# numpad.net
KiCad netlist of a schematic drawn in EAGLE
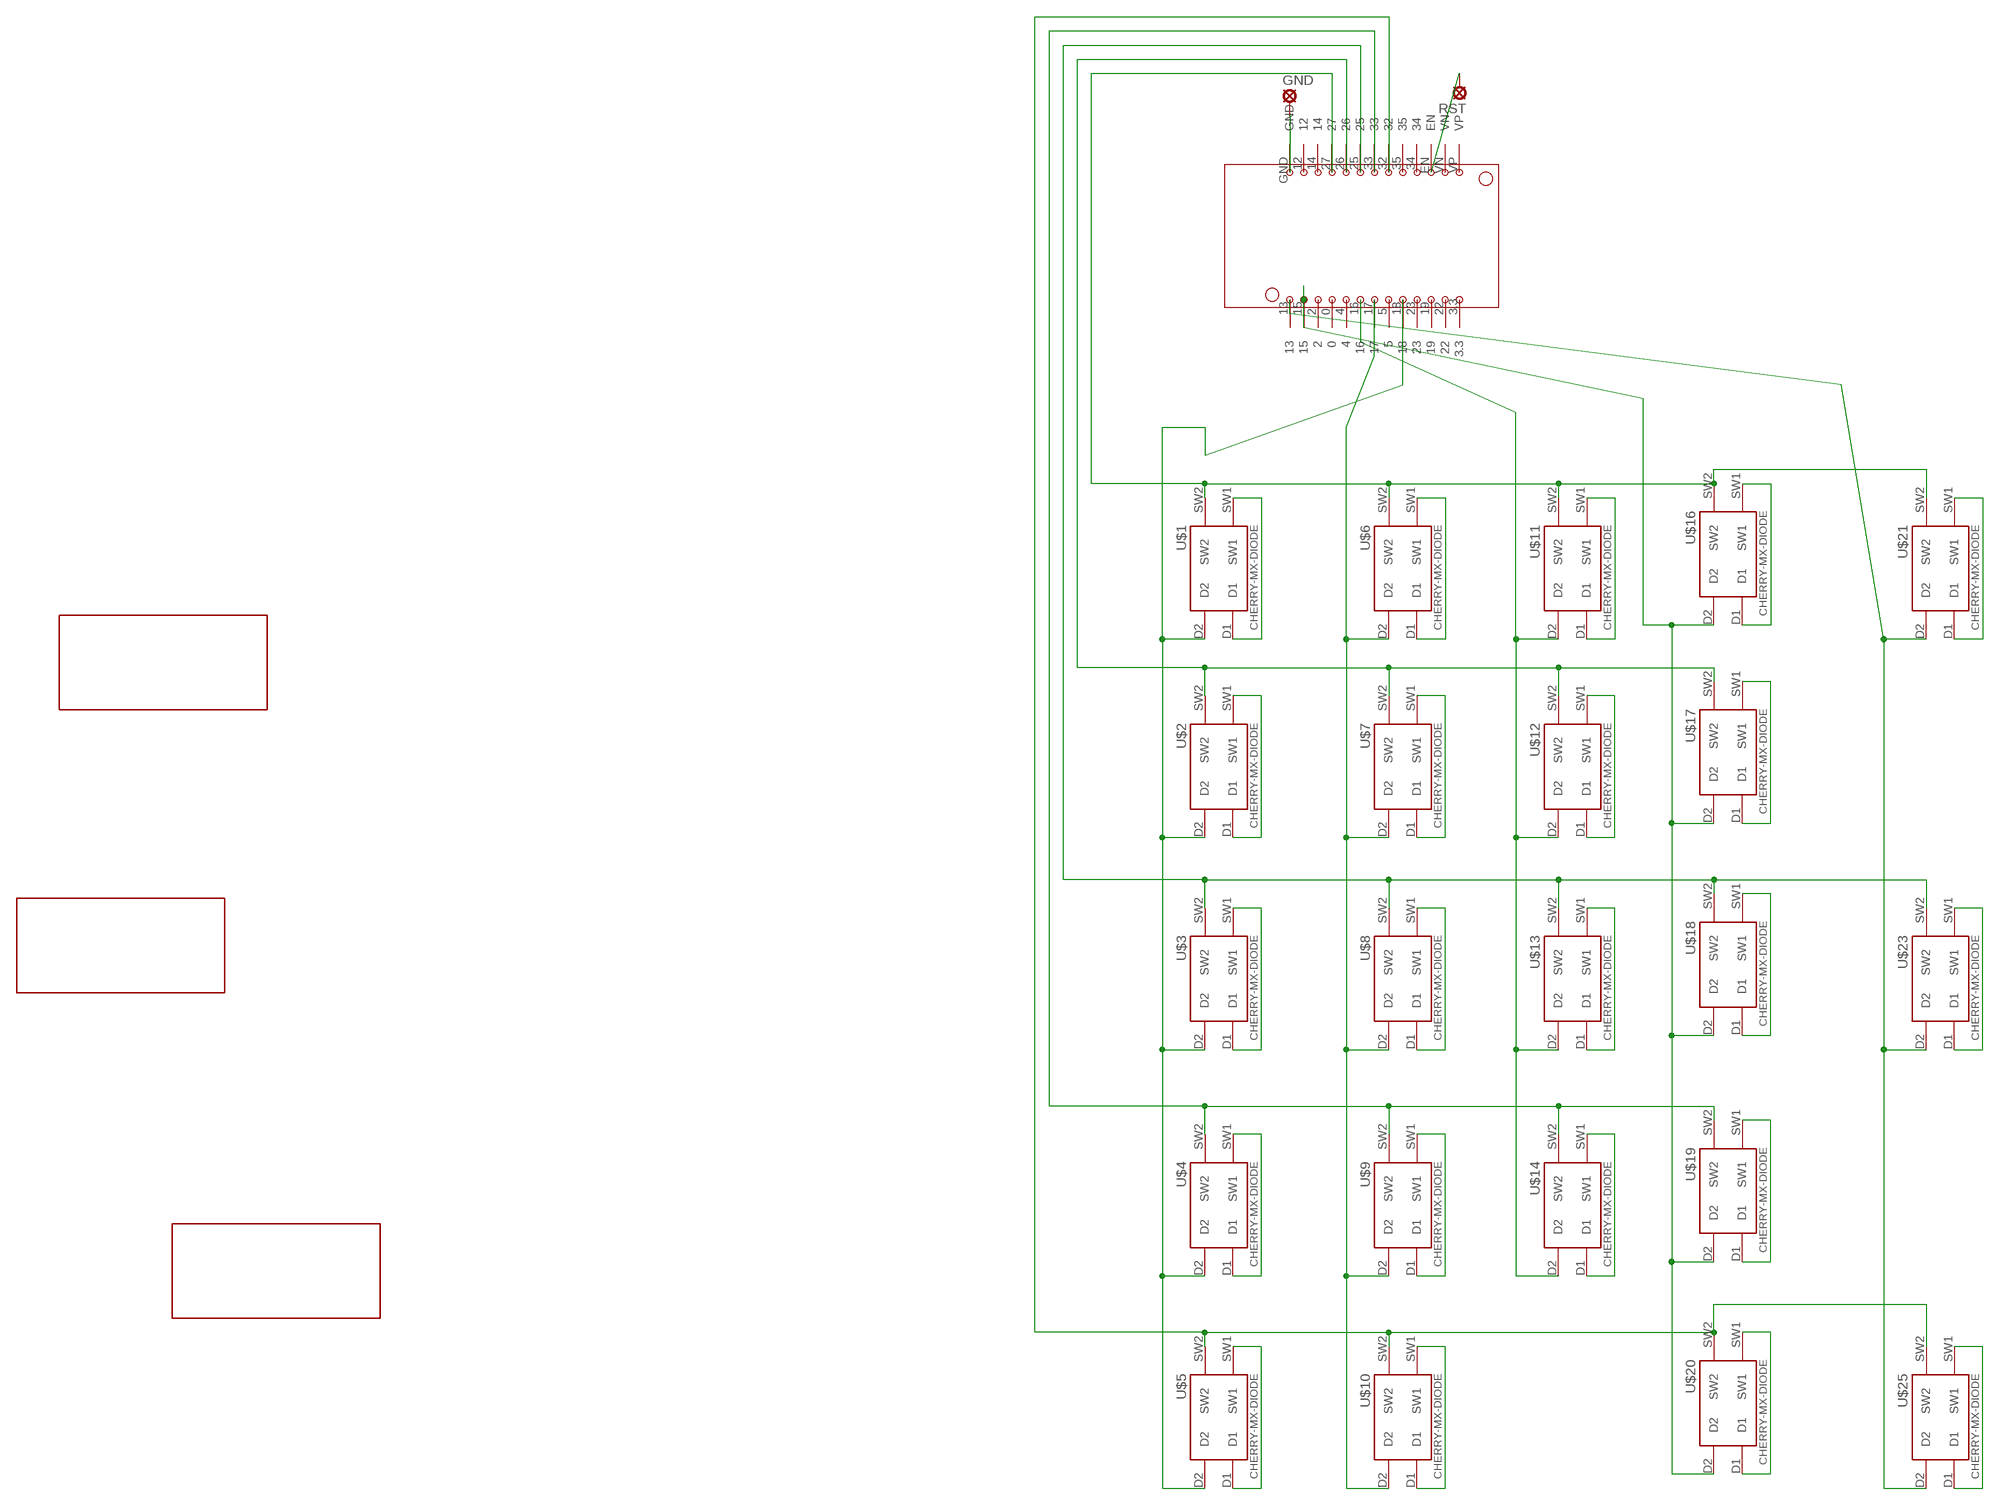
[diagram p0: schematic, sheet 1]

(export (version "E")
  (design (tool "Eeschema 10.0.6"))
  (components
    (comp (ref "GND")
      (value "LSP10")
      (footprint "eagle-import:LSP10")
      (libsource (lib "eagle-import") (part "LSP10"))
    )
    (comp (ref "RST")
      (value "LSP10")
      (footprint "eagle-import:LSP10")
      (libsource (lib "eagle-import") (part "LSP10"))
    )
    (comp (ref "U$1")
      (value "CHERRY-MX-DIODE")
      (footprint "eagle-import:CHERRY-MX-DIODE")
      (libsource (lib "eagle-import") (part "CHERRY-MX-DIODE"))
    )
    (comp (ref "U$2")
      (value "CHERRY-MX-DIODE")
      (footprint "eagle-import:CHERRY-MX-DIODE")
      (libsource (lib "eagle-import") (part "CHERRY-MX-DIODE"))
    )
    (comp (ref "U$3")
      (value "CHERRY-MX-DIODE")
      (footprint "eagle-import:CHERRY-MX-DIODE")
      (libsource (lib "eagle-import") (part "CHERRY-MX-DIODE"))
    )
    (comp (ref "U$4")
      (value "CHERRY-MX-DIODE")
      (footprint "eagle-import:CHERRY-MX-DIODE")
      (libsource (lib "eagle-import") (part "CHERRY-MX-DIODE"))
    )
    (comp (ref "U$5")
      (value "CHERRY-MX-DIODE")
      (footprint "eagle-import:CHERRY-MX-DIODE")
      (libsource (lib "eagle-import") (part "CHERRY-MX-DIODE"))
    )
    (comp (ref "U$6")
      (value "CHERRY-MX-DIODE")
      (footprint "eagle-import:CHERRY-MX-DIODE")
      (libsource (lib "eagle-import") (part "CHERRY-MX-DIODE"))
    )
    (comp (ref "U$7")
      (value "CHERRY-MX-DIODE")
      (footprint "eagle-import:CHERRY-MX-DIODE")
      (libsource (lib "eagle-import") (part "CHERRY-MX-DIODE"))
    )
    (comp (ref "U$8")
      (value "CHERRY-MX-DIODE")
      (footprint "eagle-import:CHERRY-MX-DIODE")
      (libsource (lib "eagle-import") (part "CHERRY-MX-DIODE"))
    )
    (comp (ref "U$9")
      (value "CHERRY-MX-DIODE")
      (footprint "eagle-import:CHERRY-MX-DIODE")
      (libsource (lib "eagle-import") (part "CHERRY-MX-DIODE"))
    )
    (comp (ref "U$10")
      (value "CHERRY-MX-DIODE")
      (footprint "eagle-import:CHERRY-MX-DIODE")
      (libsource (lib "eagle-import") (part "CHERRY-MX-DIODE"))
    )
    (comp (ref "U$11")
      (value "CHERRY-MX-DIODE")
      (footprint "eagle-import:CHERRY-MX-DIODE")
      (libsource (lib "eagle-import") (part "CHERRY-MX-DIODE"))
    )
    (comp (ref "U$12")
      (value "CHERRY-MX-DIODE")
      (footprint "eagle-import:CHERRY-MX-DIODE")
      (libsource (lib "eagle-import") (part "CHERRY-MX-DIODE"))
    )
    (comp (ref "U$13")
      (value "CHERRY-MX-DIODE")
      (footprint "eagle-import:CHERRY-MX-DIODE")
      (libsource (lib "eagle-import") (part "CHERRY-MX-DIODE"))
    )
    (comp (ref "U$14")
      (value "CHERRY-MX-DIODE")
      (footprint "eagle-import:CHERRY-MX-DIODE")
      (libsource (lib "eagle-import") (part "CHERRY-MX-DIODE"))
    )
    (comp (ref "U$15")
      (value "2U")
      (footprint "eagle-import:2U")
      (libsource (lib "eagle-import") (part "2U"))
    )
    (comp (ref "U$16")
      (value "CHERRY-MX-DIODE")
      (footprint "eagle-import:CHERRY-MX-DIODE")
      (libsource (lib "eagle-import") (part "CHERRY-MX-DIODE"))
    )
    (comp (ref "U$17")
      (value "CHERRY-MX-DIODE")
      (footprint "eagle-import:CHERRY-MX-DIODE")
      (libsource (lib "eagle-import") (part "CHERRY-MX-DIODE"))
    )
    (comp (ref "U$18")
      (value "CHERRY-MX-DIODE")
      (footprint "eagle-import:CHERRY-MX-DIODE")
      (libsource (lib "eagle-import") (part "CHERRY-MX-DIODE"))
    )
    (comp (ref "U$19")
      (value "CHERRY-MX-DIODE")
      (footprint "eagle-import:CHERRY-MX-DIODE")
      (libsource (lib "eagle-import") (part "CHERRY-MX-DIODE"))
    )
    (comp (ref "U$20")
      (value "CHERRY-MX-DIODE")
      (footprint "eagle-import:CHERRY-MX-DIODE")
      (libsource (lib "eagle-import") (part "CHERRY-MX-DIODE"))
    )
    (comp (ref "U$21")
      (value "CHERRY-MX-DIODE")
      (footprint "eagle-import:CHERRY-MX-DIODE")
      (libsource (lib "eagle-import") (part "CHERRY-MX-DIODE"))
    )
    (comp (ref "U$22")
      (value "2U")
      (footprint "eagle-import:2U")
      (libsource (lib "eagle-import") (part "2U"))
    )
    (comp (ref "U$23")
      (value "CHERRY-MX-DIODE")
      (footprint "eagle-import:CHERRY-MX-DIODE")
      (libsource (lib "eagle-import") (part "CHERRY-MX-DIODE"))
    )
    (comp (ref "U$24")
      (value "2U")
      (footprint "eagle-import:2U")
      (libsource (lib "eagle-import") (part "2U"))
    )
    (comp (ref "U$25")
      (value "CHERRY-MX-DIODE")
      (footprint "eagle-import:CHERRY-MX-DIODE")
      (libsource (lib "eagle-import") (part "CHERRY-MX-DIODE"))
    )
    (comp (ref "U$27")
      (value "ESP32OFFBRAND")
      (footprint "eagle-import:ESP32OFFBRAND")
      (libsource (lib "eagle-import") (part "ESP32OFFBRAND"))
    )
  )
  (nets
    (net (code "1") (name "Net-(GND-PadMP)") (class "Default")
      (node (ref "GND") (pin "MP") (pinfunction "MP_MP") (pintype "passive"))
      (node (ref "U$27") (pin "GND") (pinfunction "GND_GND") (pintype "bidirectional"))
    )
    (net (code "2") (name "Net-(RST-PadMP)") (class "Default")
      (node (ref "RST") (pin "MP") (pinfunction "MP_MP") (pintype "passive"))
      (node (ref "U$27") (pin "EN") (pinfunction "EN_EN") (pintype "bidirectional"))
    )
    (net (code "3") (name "Net-(U$1-PadD1)") (class "Default")
      (node (ref "U$1") (pin "D1") (pinfunction "D1_D1") (pintype "bidirectional"))
      (node (ref "U$1") (pin "SW1") (pinfunction "SW1_SW1") (pintype "bidirectional"))
    )
    (net (code "4") (name "Net-(U$1-PadD2)") (class "Default")
      (node (ref "U$1") (pin "D2") (pinfunction "D2_D2") (pintype "bidirectional"))
      (node (ref "U$2") (pin "D2") (pinfunction "D2_D2") (pintype "bidirectional"))
      (node (ref "U$27") (pin "18") (pinfunction "18_18") (pintype "bidirectional"))
      (node (ref "U$3") (pin "D2") (pinfunction "D2_D2") (pintype "bidirectional"))
      (node (ref "U$4") (pin "D2") (pinfunction "D2_D2") (pintype "bidirectional"))
      (node (ref "U$5") (pin "D2") (pinfunction "D2_D2") (pintype "bidirectional"))
    )
    (net (code "5") (name "Net-(U$1-PadSW2)") (class "Default")
      (node (ref "U$1") (pin "SW2") (pinfunction "SW2_SW2") (pintype "bidirectional"))
      (node (ref "U$11") (pin "SW2") (pinfunction "SW2_SW2") (pintype "bidirectional"))
      (node (ref "U$16") (pin "SW2") (pinfunction "SW2_SW2") (pintype "bidirectional"))
      (node (ref "U$21") (pin "SW2") (pinfunction "SW2_SW2") (pintype "bidirectional"))
      (node (ref "U$27") (pin "27") (pinfunction "27_27") (pintype "bidirectional"))
      (node (ref "U$6") (pin "SW2") (pinfunction "SW2_SW2") (pintype "bidirectional"))
    )
    (net (code "6") (name "Net-(U$2-PadD1)") (class "Default")
      (node (ref "U$2") (pin "D1") (pinfunction "D1_D1") (pintype "bidirectional"))
      (node (ref "U$2") (pin "SW1") (pinfunction "SW1_SW1") (pintype "bidirectional"))
    )
    (net (code "7") (name "Net-(U$3-PadD1)") (class "Default")
      (node (ref "U$3") (pin "D1") (pinfunction "D1_D1") (pintype "bidirectional"))
      (node (ref "U$3") (pin "SW1") (pinfunction "SW1_SW1") (pintype "bidirectional"))
    )
    (net (code "8") (name "Net-(U$4-PadD1)") (class "Default")
      (node (ref "U$4") (pin "D1") (pinfunction "D1_D1") (pintype "bidirectional"))
      (node (ref "U$4") (pin "SW1") (pinfunction "SW1_SW1") (pintype "bidirectional"))
    )
    (net (code "9") (name "Net-(U$5-PadD1)") (class "Default")
      (node (ref "U$5") (pin "D1") (pinfunction "D1_D1") (pintype "bidirectional"))
      (node (ref "U$5") (pin "SW1") (pinfunction "SW1_SW1") (pintype "bidirectional"))
    )
    (net (code "10") (name "Net-(U$6-PadD1)") (class "Default")
      (node (ref "U$6") (pin "D1") (pinfunction "D1_D1") (pintype "bidirectional"))
      (node (ref "U$6") (pin "SW1") (pinfunction "SW1_SW1") (pintype "bidirectional"))
    )
    (net (code "11") (name "Net-(U$7-PadD1)") (class "Default")
      (node (ref "U$7") (pin "D1") (pinfunction "D1_D1") (pintype "bidirectional"))
      (node (ref "U$7") (pin "SW1") (pinfunction "SW1_SW1") (pintype "bidirectional"))
    )
    (net (code "12") (name "Net-(U$8-PadD1)") (class "Default")
      (node (ref "U$8") (pin "D1") (pinfunction "D1_D1") (pintype "bidirectional"))
      (node (ref "U$8") (pin "SW1") (pinfunction "SW1_SW1") (pintype "bidirectional"))
    )
    (net (code "13") (name "Net-(U$9-PadD1)") (class "Default")
      (node (ref "U$9") (pin "D1") (pinfunction "D1_D1") (pintype "bidirectional"))
      (node (ref "U$9") (pin "SW1") (pinfunction "SW1_SW1") (pintype "bidirectional"))
    )
    (net (code "14") (name "Net-(U$10-PadD1)") (class "Default")
      (node (ref "U$10") (pin "D1") (pinfunction "D1_D1") (pintype "bidirectional"))
      (node (ref "U$10") (pin "SW1") (pinfunction "SW1_SW1") (pintype "bidirectional"))
    )
    (net (code "15") (name "Net-(U$10-PadD2)") (class "Default")
      (node (ref "U$10") (pin "D2") (pinfunction "D2_D2") (pintype "bidirectional"))
      (node (ref "U$27") (pin "17") (pinfunction "17_17") (pintype "bidirectional"))
      (node (ref "U$6") (pin "D2") (pinfunction "D2_D2") (pintype "bidirectional"))
      (node (ref "U$7") (pin "D2") (pinfunction "D2_D2") (pintype "bidirectional"))
      (node (ref "U$8") (pin "D2") (pinfunction "D2_D2") (pintype "bidirectional"))
      (node (ref "U$9") (pin "D2") (pinfunction "D2_D2") (pintype "bidirectional"))
    )
    (net (code "16") (name "Net-(U$10-PadSW2)") (class "Default")
      (node (ref "U$10") (pin "SW2") (pinfunction "SW2_SW2") (pintype "bidirectional"))
      (node (ref "U$20") (pin "SW2") (pinfunction "SW2_SW2") (pintype "bidirectional"))
      (node (ref "U$25") (pin "SW2") (pinfunction "SW2_SW2") (pintype "bidirectional"))
      (node (ref "U$27") (pin "32") (pinfunction "32_32") (pintype "bidirectional"))
      (node (ref "U$5") (pin "SW2") (pinfunction "SW2_SW2") (pintype "bidirectional"))
    )
    (net (code "17") (name "Net-(U$11-PadD1)") (class "Default")
      (node (ref "U$11") (pin "D1") (pinfunction "D1_D1") (pintype "bidirectional"))
      (node (ref "U$11") (pin "SW1") (pinfunction "SW1_SW1") (pintype "bidirectional"))
    )
    (net (code "18") (name "Net-(U$11-PadD2)") (class "Default")
      (node (ref "U$11") (pin "D2") (pinfunction "D2_D2") (pintype "bidirectional"))
      (node (ref "U$12") (pin "D2") (pinfunction "D2_D2") (pintype "bidirectional"))
      (node (ref "U$13") (pin "D2") (pinfunction "D2_D2") (pintype "bidirectional"))
      (node (ref "U$14") (pin "D2") (pinfunction "D2_D2") (pintype "bidirectional"))
      (node (ref "U$27") (pin "16") (pinfunction "16_16") (pintype "bidirectional"))
    )
    (net (code "19") (name "Net-(U$12-PadD1)") (class "Default")
      (node (ref "U$12") (pin "D1") (pinfunction "D1_D1") (pintype "bidirectional"))
      (node (ref "U$12") (pin "SW1") (pinfunction "SW1_SW1") (pintype "bidirectional"))
    )
    (net (code "20") (name "Net-(U$12-PadSW2)") (class "Default")
      (node (ref "U$12") (pin "SW2") (pinfunction "SW2_SW2") (pintype "bidirectional"))
      (node (ref "U$17") (pin "SW2") (pinfunction "SW2_SW2") (pintype "bidirectional"))
      (node (ref "U$2") (pin "SW2") (pinfunction "SW2_SW2") (pintype "bidirectional"))
      (node (ref "U$27") (pin "26") (pinfunction "26_26") (pintype "bidirectional"))
      (node (ref "U$7") (pin "SW2") (pinfunction "SW2_SW2") (pintype "bidirectional"))
    )
    (net (code "21") (name "Net-(U$13-PadD1)") (class "Default")
      (node (ref "U$13") (pin "D1") (pinfunction "D1_D1") (pintype "bidirectional"))
      (node (ref "U$13") (pin "SW1") (pinfunction "SW1_SW1") (pintype "bidirectional"))
    )
    (net (code "22") (name "Net-(U$13-PadSW2)") (class "Default")
      (node (ref "U$13") (pin "SW2") (pinfunction "SW2_SW2") (pintype "bidirectional"))
      (node (ref "U$18") (pin "SW2") (pinfunction "SW2_SW2") (pintype "bidirectional"))
      (node (ref "U$23") (pin "SW2") (pinfunction "SW2_SW2") (pintype "bidirectional"))
      (node (ref "U$27") (pin "25") (pinfunction "25_25") (pintype "bidirectional"))
      (node (ref "U$3") (pin "SW2") (pinfunction "SW2_SW2") (pintype "bidirectional"))
      (node (ref "U$8") (pin "SW2") (pinfunction "SW2_SW2") (pintype "bidirectional"))
    )
    (net (code "23") (name "Net-(U$14-PadD1)") (class "Default")
      (node (ref "U$14") (pin "D1") (pinfunction "D1_D1") (pintype "bidirectional"))
      (node (ref "U$14") (pin "SW1") (pinfunction "SW1_SW1") (pintype "bidirectional"))
    )
    (net (code "24") (name "Net-(U$14-PadSW2)") (class "Default")
      (node (ref "U$14") (pin "SW2") (pinfunction "SW2_SW2") (pintype "bidirectional"))
      (node (ref "U$19") (pin "SW2") (pinfunction "SW2_SW2") (pintype "bidirectional"))
      (node (ref "U$27") (pin "33") (pinfunction "33_33") (pintype "bidirectional"))
      (node (ref "U$4") (pin "SW2") (pinfunction "SW2_SW2") (pintype "bidirectional"))
      (node (ref "U$9") (pin "SW2") (pinfunction "SW2_SW2") (pintype "bidirectional"))
    )
    (net (code "25") (name "Net-(U$16-PadD1)") (class "Default")
      (node (ref "U$16") (pin "D1") (pinfunction "D1_D1") (pintype "bidirectional"))
      (node (ref "U$16") (pin "SW1") (pinfunction "SW1_SW1") (pintype "bidirectional"))
    )
    (net (code "26") (name "Net-(U$16-PadD2)") (class "Default")
      (node (ref "U$16") (pin "D2") (pinfunction "D2_D2") (pintype "bidirectional"))
      (node (ref "U$17") (pin "D2") (pinfunction "D2_D2") (pintype "bidirectional"))
      (node (ref "U$18") (pin "D2") (pinfunction "D2_D2") (pintype "bidirectional"))
      (node (ref "U$19") (pin "D2") (pinfunction "D2_D2") (pintype "bidirectional"))
      (node (ref "U$20") (pin "D2") (pinfunction "D2_D2") (pintype "bidirectional"))
      (node (ref "U$27") (pin "15") (pinfunction "15_15") (pintype "bidirectional"))
    )
    (net (code "27") (name "Net-(U$17-PadD1)") (class "Default")
      (node (ref "U$17") (pin "D1") (pinfunction "D1_D1") (pintype "bidirectional"))
      (node (ref "U$17") (pin "SW1") (pinfunction "SW1_SW1") (pintype "bidirectional"))
    )
    (net (code "28") (name "Net-(U$18-PadD1)") (class "Default")
      (node (ref "U$18") (pin "D1") (pinfunction "D1_D1") (pintype "bidirectional"))
      (node (ref "U$18") (pin "SW1") (pinfunction "SW1_SW1") (pintype "bidirectional"))
    )
    (net (code "29") (name "Net-(U$19-PadD1)") (class "Default")
      (node (ref "U$19") (pin "D1") (pinfunction "D1_D1") (pintype "bidirectional"))
      (node (ref "U$19") (pin "SW1") (pinfunction "SW1_SW1") (pintype "bidirectional"))
    )
    (net (code "30") (name "Net-(U$20-PadD1)") (class "Default")
      (node (ref "U$20") (pin "D1") (pinfunction "D1_D1") (pintype "bidirectional"))
      (node (ref "U$20") (pin "SW1") (pinfunction "SW1_SW1") (pintype "bidirectional"))
    )
    (net (code "31") (name "Net-(U$21-PadD1)") (class "Default")
      (node (ref "U$21") (pin "D1") (pinfunction "D1_D1") (pintype "bidirectional"))
      (node (ref "U$21") (pin "SW1") (pinfunction "SW1_SW1") (pintype "bidirectional"))
    )
    (net (code "32") (name "Net-(U$21-PadD2)") (class "Default")
      (node (ref "U$21") (pin "D2") (pinfunction "D2_D2") (pintype "bidirectional"))
      (node (ref "U$23") (pin "D2") (pinfunction "D2_D2") (pintype "bidirectional"))
      (node (ref "U$25") (pin "D2") (pinfunction "D2_D2") (pintype "bidirectional"))
      (node (ref "U$27") (pin "13") (pinfunction "13_13") (pintype "bidirectional"))
    )
    (net (code "33") (name "Net-(U$23-PadD1)") (class "Default")
      (node (ref "U$23") (pin "D1") (pinfunction "D1_D1") (pintype "bidirectional"))
      (node (ref "U$23") (pin "SW1") (pinfunction "SW1_SW1") (pintype "bidirectional"))
    )
    (net (code "34") (name "Net-(U$25-PadD1)") (class "Default")
      (node (ref "U$25") (pin "D1") (pinfunction "D1_D1") (pintype "bidirectional"))
      (node (ref "U$25") (pin "SW1") (pinfunction "SW1_SW1") (pintype "bidirectional"))
    )
    (net (code "35") (name "unconnected-(U$27-Pad0)") (class "Default")
      (node (ref "U$27") (pin "0") (pinfunction "0_0") (pintype "bidirectional"))
    )
    (net (code "36") (name "unconnected-(U$27-Pad2)") (class "Default")
      (node (ref "U$27") (pin "2") (pinfunction "2_2") (pintype "bidirectional"))
    )
    (net (code "37") (name "unconnected-(U$27-Pad3.3)") (class "Default")
      (node (ref "U$27") (pin "3.3") (pinfunction "3.3_3.3") (pintype "bidirectional"))
    )
    (net (code "38") (name "unconnected-(U$27-Pad4)") (class "Default")
      (node (ref "U$27") (pin "4") (pinfunction "4_4") (pintype "bidirectional"))
    )
    (net (code "39") (name "unconnected-(U$27-Pad5)") (class "Default")
      (node (ref "U$27") (pin "5") (pinfunction "5_5") (pintype "bidirectional"))
    )
    (net (code "40") (name "unconnected-(U$27-Pad12)") (class "Default")
      (node (ref "U$27") (pin "12") (pinfunction "12_12") (pintype "bidirectional"))
    )
    (net (code "41") (name "unconnected-(U$27-Pad14)") (class "Default")
      (node (ref "U$27") (pin "14") (pinfunction "14_14") (pintype "bidirectional"))
    )
    (net (code "42") (name "unconnected-(U$27-Pad19)") (class "Default")
      (node (ref "U$27") (pin "19") (pinfunction "19_19") (pintype "bidirectional"))
    )
    (net (code "43") (name "unconnected-(U$27-Pad22)") (class "Default")
      (node (ref "U$27") (pin "22") (pinfunction "22_22") (pintype "bidirectional"))
    )
    (net (code "44") (name "unconnected-(U$27-Pad23)") (class "Default")
      (node (ref "U$27") (pin "23") (pinfunction "23_23") (pintype "bidirectional"))
    )
    (net (code "45") (name "unconnected-(U$27-Pad34)") (class "Default")
      (node (ref "U$27") (pin "34") (pinfunction "34_34") (pintype "bidirectional"))
    )
    (net (code "46") (name "unconnected-(U$27-Pad35)") (class "Default")
      (node (ref "U$27") (pin "35") (pinfunction "35_35") (pintype "bidirectional"))
    )
    (net (code "47") (name "unconnected-(U$27-PadVN)") (class "Default")
      (node (ref "U$27") (pin "VN") (pinfunction "VN_VN") (pintype "bidirectional"))
    )
    (net (code "48") (name "unconnected-(U$27-PadVP)") (class "Default")
      (node (ref "U$27") (pin "VP") (pinfunction "VP_VP") (pintype "bidirectional"))
    )
  )
)
